# schematic.net
KiCad netlist of a schematic drawn in EAGLE
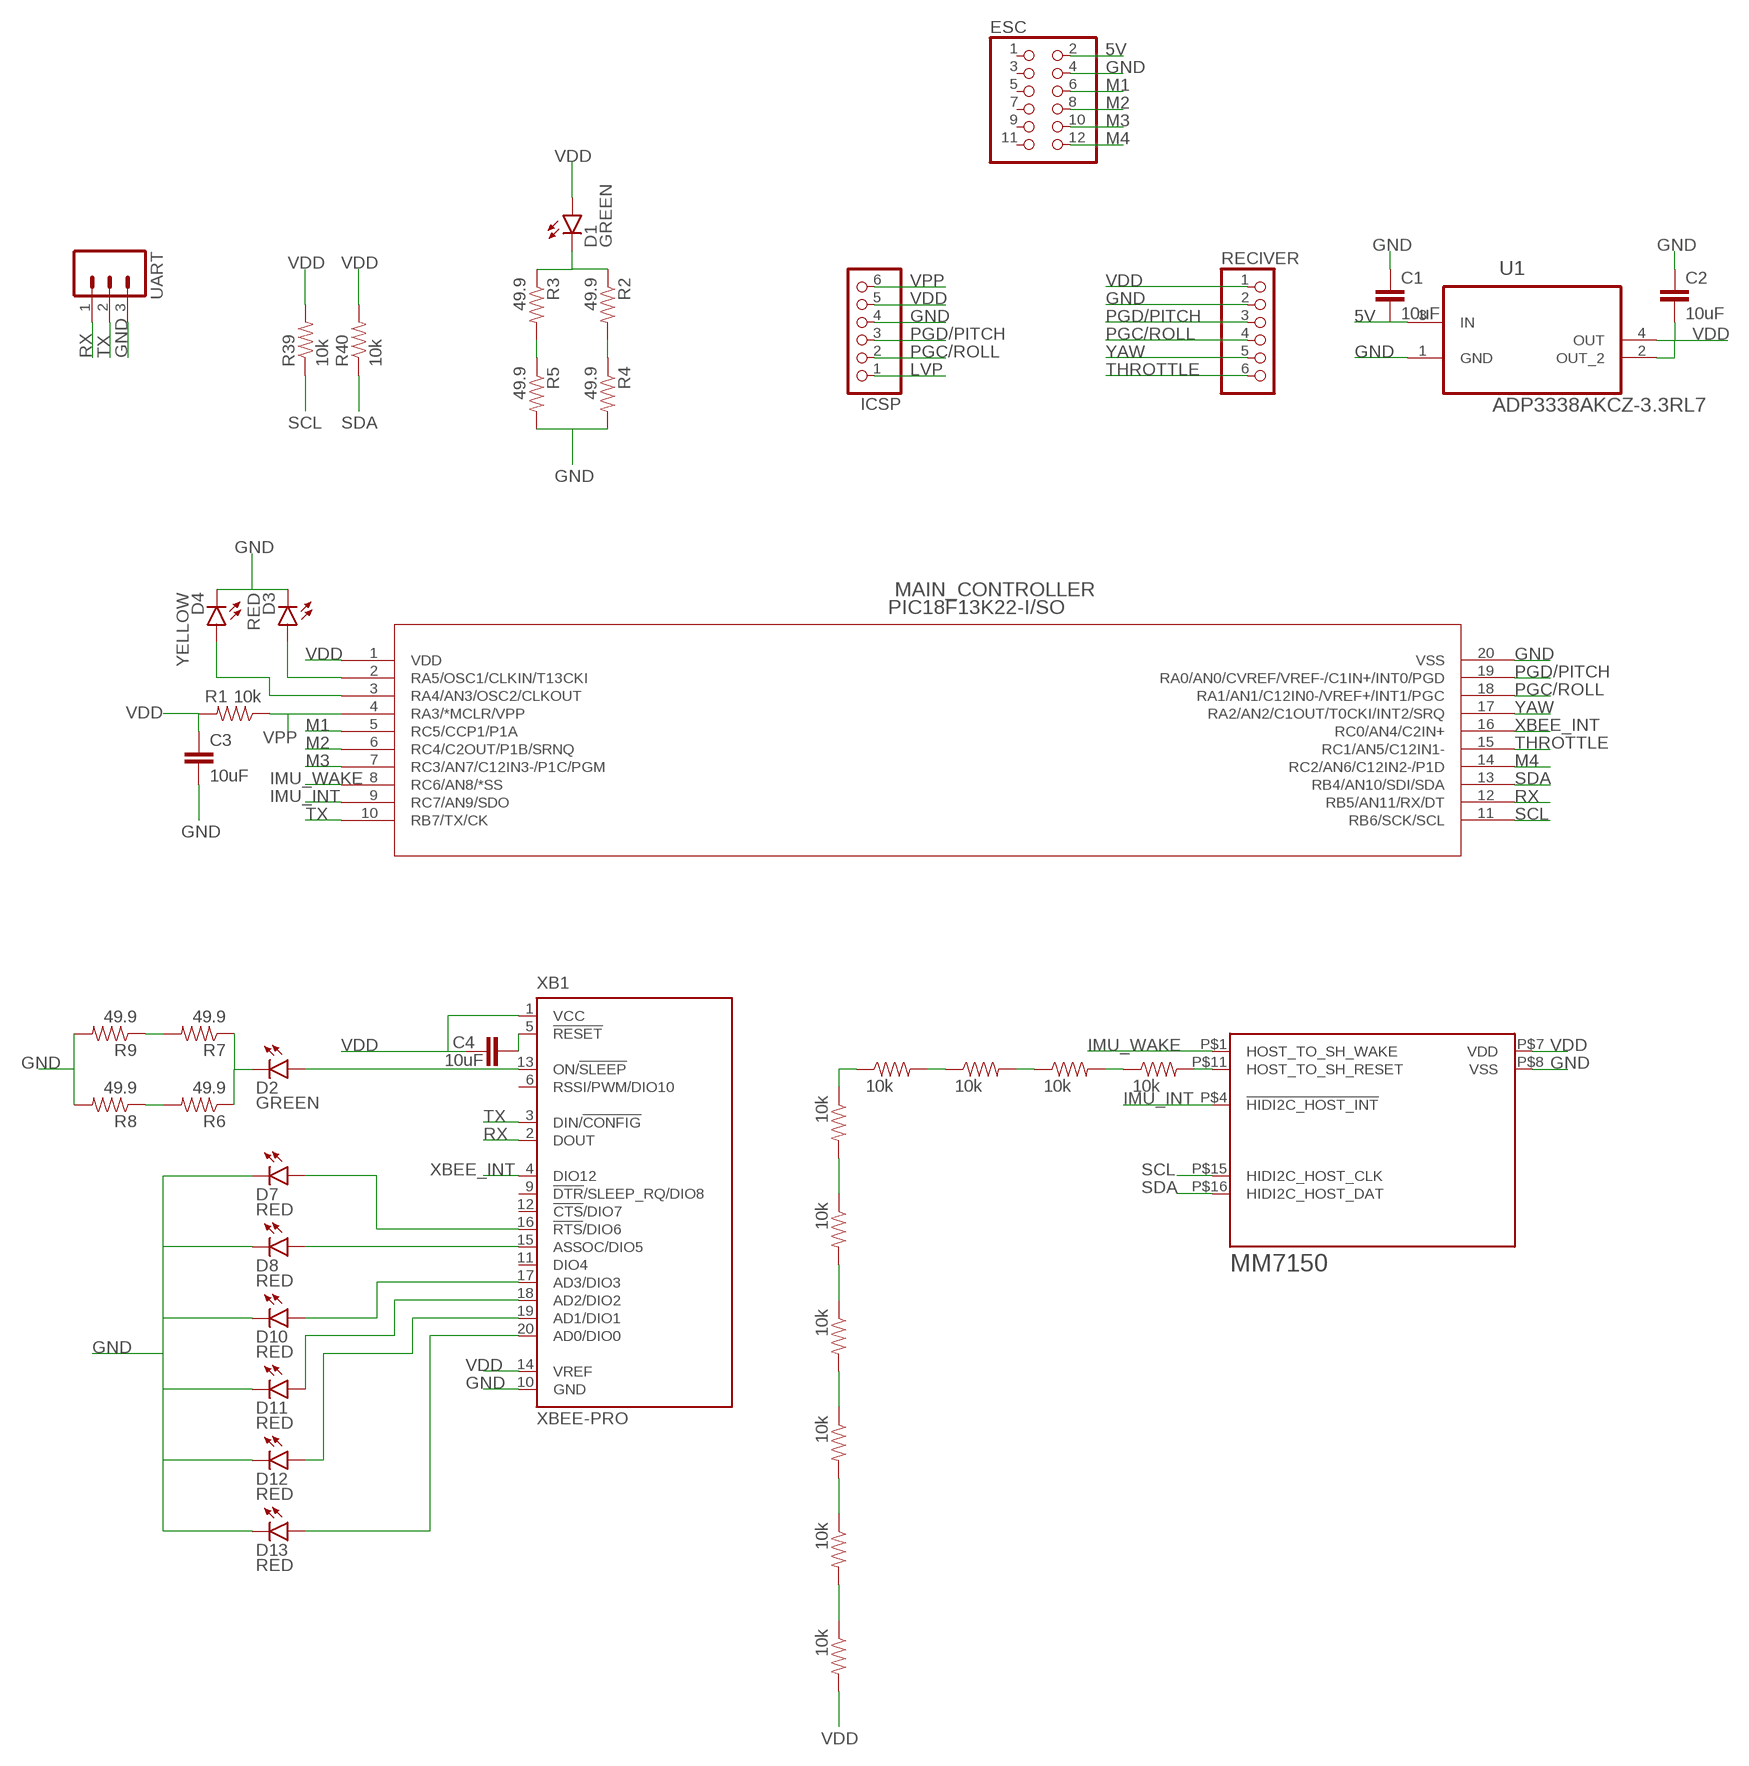
[diagram p0: schematic, sheet 1]

(export (version "E")
  (design (tool "Eeschema 10.0.6"))
  (components
    (comp (ref "C1")
      (value "10uF")
      (footprint "eagle-import:1210")
      (libsource (lib "eagle-import") (part "10UF50V20%(1210)"))
    )
    (comp (ref "C2")
      (value "10uF")
      (footprint "eagle-import:1210")
      (libsource (lib "eagle-import") (part "10UF50V20%(1210)"))
    )
    (comp (ref "C3")
      (value "10uF")
      (footprint "eagle-import:1210")
      (libsource (lib "eagle-import") (part "10UF50V20%(1210)"))
    )
    (comp (ref "C4")
      (value "10uF")
      (footprint "eagle-import:1210")
      (libsource (lib "eagle-import") (part "10UF50V20%(1210)"))
    )
    (comp (ref "D1")
      (value "GREEN")
      (footprint "eagle-import:LED-1206")
      (libsource (lib "eagle-import") (part "LED-GREEN1206"))
    )
    (comp (ref "D2")
      (value "GREEN")
      (footprint "eagle-import:LED-1206")
      (libsource (lib "eagle-import") (part "LED-GREEN1206"))
    )
    (comp (ref "D3")
      (value "RED")
      (footprint "eagle-import:LED-1206")
      (libsource (lib "eagle-import") (part "LED-RED1206"))
    )
    (comp (ref "D4")
      (value "YELLOW")
      (footprint "eagle-import:LED-1206")
      (libsource (lib "eagle-import") (part "LED-YELLOW1206"))
    )
    (comp (ref "D7")
      (value "RED")
      (footprint "eagle-import:LED-1206")
      (libsource (lib "eagle-import") (part "LED-RED1206"))
    )
    (comp (ref "D8")
      (value "RED")
      (footprint "eagle-import:LED-1206")
      (libsource (lib "eagle-import") (part "LED-RED1206"))
    )
    (comp (ref "D10")
      (value "RED")
      (footprint "eagle-import:LED-1206")
      (libsource (lib "eagle-import") (part "LED-RED1206"))
    )
    (comp (ref "D11")
      (value "RED")
      (footprint "eagle-import:LED-1206")
      (libsource (lib "eagle-import") (part "LED-RED1206"))
    )
    (comp (ref "D12")
      (value "RED")
      (footprint "eagle-import:LED-1206")
      (libsource (lib "eagle-import") (part "LED-RED1206"))
    )
    (comp (ref "D13")
      (value "RED")
      (footprint "eagle-import:LED-1206")
      (libsource (lib "eagle-import") (part "LED-RED1206"))
    )
    (comp (ref "ESC")
      (value "PINHD-2X6")
      (footprint "eagle-import:2X06")
      (libsource (lib "eagle-import") (part "PINHD-2X6"))
    )
    (comp (ref "ICSP")
      (value "PINHD-1X6/90")
      (footprint "eagle-import:1X06_90")
      (libsource (lib "eagle-import") (part "PINHD-1X6/90"))
    )
    (comp (ref "IMU")
      (value "MM7150")
      (footprint "eagle-import:LANDPATTERN")
      (libsource (lib "eagle-import") (part "MM7150"))
    )
    (comp (ref "MAIN_CONTROLLER")
      (value "PIC18F13K22-I/SO")
      (footprint "eagle-import:PIC18F13K22-X_SO")
      (libsource (lib "eagle-import") (part "PIC18F13K22-I/SO"))
    )
    (comp (ref "R1")
      (value "10k")
      (footprint "eagle-import:0402-RES")
      (libsource (lib "eagle-import") (part "RESISTOR0402-RES"))
    )
    (comp (ref "R2")
      (value "49.9")
      (footprint "eagle-import:0402-RES")
      (libsource (lib "eagle-import") (part "RESISTOR0402-RES"))
    )
    (comp (ref "R3")
      (value "49.9")
      (footprint "eagle-import:0402-RES")
      (libsource (lib "eagle-import") (part "RESISTOR0402-RES"))
    )
    (comp (ref "R4")
      (value "49.9")
      (footprint "eagle-import:0402-RES")
      (libsource (lib "eagle-import") (part "RESISTOR0402-RES"))
    )
    (comp (ref "R5")
      (value "49.9")
      (footprint "eagle-import:0402-RES")
      (libsource (lib "eagle-import") (part "RESISTOR0402-RES"))
    )
    (comp (ref "R6")
      (value "49.9")
      (footprint "eagle-import:0402-RES")
      (libsource (lib "eagle-import") (part "RESISTOR0402-RES"))
    )
    (comp (ref "R7")
      (value "49.9")
      (footprint "eagle-import:0402-RES")
      (libsource (lib "eagle-import") (part "RESISTOR0402-RES"))
    )
    (comp (ref "R8")
      (value "49.9")
      (footprint "eagle-import:0402-RES")
      (libsource (lib "eagle-import") (part "RESISTOR0402-RES"))
    )
    (comp (ref "R9")
      (value "49.9")
      (footprint "eagle-import:0402-RES")
      (libsource (lib "eagle-import") (part "RESISTOR0402-RES"))
    )
    (comp (ref "R10")
      (value "10k")
      (footprint "eagle-import:0402-RES")
      (libsource (lib "eagle-import") (part "RESISTOR0402-RES"))
    )
    (comp (ref "R11")
      (value "10k")
      (footprint "eagle-import:0402-RES")
      (libsource (lib "eagle-import") (part "RESISTOR0402-RES"))
    )
    (comp (ref "R12")
      (value "10k")
      (footprint "eagle-import:0402-RES")
      (libsource (lib "eagle-import") (part "RESISTOR0402-RES"))
    )
    (comp (ref "R13")
      (value "10k")
      (footprint "eagle-import:0402-RES")
      (libsource (lib "eagle-import") (part "RESISTOR0402-RES"))
    )
    (comp (ref "R14")
      (value "10k")
      (footprint "eagle-import:0402-RES")
      (libsource (lib "eagle-import") (part "RESISTOR0402-RES"))
    )
    (comp (ref "R15")
      (value "10k")
      (footprint "eagle-import:0402-RES")
      (libsource (lib "eagle-import") (part "RESISTOR0402-RES"))
    )
    (comp (ref "R16")
      (value "10k")
      (footprint "eagle-import:0402-RES")
      (libsource (lib "eagle-import") (part "RESISTOR0402-RES"))
    )
    (comp (ref "R17")
      (value "10k")
      (footprint "eagle-import:0402-RES")
      (libsource (lib "eagle-import") (part "RESISTOR0402-RES"))
    )
    (comp (ref "R18")
      (value "10k")
      (footprint "eagle-import:0402-RES")
      (libsource (lib "eagle-import") (part "RESISTOR0402-RES"))
    )
    (comp (ref "R19")
      (value "10k")
      (footprint "eagle-import:0402-RES")
      (libsource (lib "eagle-import") (part "RESISTOR0402-RES"))
    )
    (comp (ref "R39")
      (value "10k")
      (footprint "eagle-import:0402-RES")
      (libsource (lib "eagle-import") (part "RESISTOR0402-RES"))
    )
    (comp (ref "R40")
      (value "10k")
      (footprint "eagle-import:0402-RES")
      (libsource (lib "eagle-import") (part "RESISTOR0402-RES"))
    )
    (comp (ref "RECIVER")
      (value "PINHD-1X6")
      (footprint "eagle-import:1X06")
      (libsource (lib "eagle-import") (part "PINHD-1X6"))
    )
    (comp (ref "U1")
      (value "ADP3338AKCZ-3.3RL7")
      (footprint "eagle-import:SOT230P700X180-4N")
      (libsource (lib "eagle-import") (part "ADP3338AKCZ-3.3RL7"))
    )
    (comp (ref "UART")
      (value "M03LONGPADS")
      (footprint "eagle-import:1X03_LONGPADS")
      (libsource (lib "eagle-import") (part "M03LONGPADS"))
    )
    (comp (ref "XB1")
      (value "XBEE-PRO")
      (footprint "eagle-import:XBEE-PRO")
      (fields (field (name "MPN") "XBP24-AWI-001"))
      (libsource (lib "eagle-import") (part "XBEE-PRO"))
    )
  )
  (nets
    (net (code "1") (name "/5V") (class "Default")
      (node (ref "C1") (pin "2") (pinfunction "2_2") (pintype "passive"))
      (node (ref "ESC") (pin "2") (pinfunction "2_2") (pintype "passive"))
      (node (ref "U1") (pin "3") (pinfunction "IN_3") (pintype "input"))
    )
    (net (code "2") (name "/GND") (class "Default")
      (node (ref "C1") (pin "1") (pinfunction "1_1") (pintype "passive"))
      (node (ref "C2") (pin "1") (pinfunction "1_1") (pintype "passive"))
      (node (ref "C3") (pin "2") (pinfunction "2_2") (pintype "passive"))
      (node (ref "D10") (pin "C") (pinfunction "C_C") (pintype "passive"))
      (node (ref "D11") (pin "C") (pinfunction "C_C") (pintype "passive"))
      (node (ref "D12") (pin "C") (pinfunction "C_C") (pintype "passive"))
      (node (ref "D13") (pin "C") (pinfunction "C_C") (pintype "passive"))
      (node (ref "D3") (pin "C") (pinfunction "C_C") (pintype "passive"))
      (node (ref "D4") (pin "C") (pinfunction "C_C") (pintype "passive"))
      (node (ref "D7") (pin "C") (pinfunction "C_C") (pintype "passive"))
      (node (ref "D8") (pin "C") (pinfunction "C_C") (pintype "passive"))
      (node (ref "ESC") (pin "4") (pinfunction "4_4") (pintype "passive"))
      (node (ref "ICSP") (pin "4") (pinfunction "4_4") (pintype "passive"))
      (node (ref "IMU") (pin "P$8") (pinfunction "VSS_P$8") (pintype "power_in"))
      (node (ref "MAIN_CONTROLLER") (pin "20") (pinfunction "VSS_20") (pintype "power_in"))
      (node (ref "R4") (pin "2") (pinfunction "2_2") (pintype "passive"))
      (node (ref "R5") (pin "2") (pinfunction "2_2") (pintype "passive"))
      (node (ref "R8") (pin "2") (pinfunction "2_2") (pintype "passive"))
      (node (ref "R9") (pin "2") (pinfunction "2_2") (pintype "passive"))
      (node (ref "RECIVER") (pin "2") (pinfunction "2_2") (pintype "passive"))
      (node (ref "U1") (pin "1") (pinfunction "GND_1") (pintype "passive"))
      (node (ref "UART") (pin "3") (pinfunction "3_3") (pintype "passive"))
      (node (ref "XB1") (pin "10") (pinfunction "GND_10") (pintype "power_in"))
    )
    (net (code "3") (name "/IMU_INT") (class "Default")
      (node (ref "IMU") (pin "P$4") (pinfunction "~{HIDI2C_HOST_INT}_P$4") (pintype "output"))
      (node (ref "MAIN_CONTROLLER") (pin "9") (pinfunction "RC7/AN9/SDO_9") (pintype "bidirectional"))
    )
    (net (code "4") (name "/IMU_WAKE") (class "Default")
      (node (ref "IMU") (pin "P$1") (pinfunction "HOST_TO_SH_WAKE_P$1") (pintype "input"))
      (node (ref "MAIN_CONTROLLER") (pin "8") (pinfunction "RC6/AN8/*SS_8") (pintype "bidirectional"))
    )
    (net (code "5") (name "/LVP") (class "Default")
      (node (ref "ICSP") (pin "1") (pinfunction "1_1") (pintype "passive"))
    )
    (net (code "6") (name "/M1") (class "Default")
      (node (ref "ESC") (pin "6") (pinfunction "6_6") (pintype "passive"))
      (node (ref "MAIN_CONTROLLER") (pin "5") (pinfunction "RC5/CCP1/P1A_5") (pintype "bidirectional"))
    )
    (net (code "7") (name "/M2") (class "Default")
      (node (ref "ESC") (pin "8") (pinfunction "8_8") (pintype "passive"))
      (node (ref "MAIN_CONTROLLER") (pin "6") (pinfunction "RC4/C2OUT/P1B/SRNQ_6") (pintype "bidirectional"))
    )
    (net (code "8") (name "/M3") (class "Default")
      (node (ref "ESC") (pin "10") (pinfunction "10_10") (pintype "passive"))
      (node (ref "MAIN_CONTROLLER") (pin "7") (pinfunction "RC3/AN7/C12IN3-/P1C/PGM_7") (pintype "bidirectional"))
    )
    (net (code "9") (name "/M4") (class "Default")
      (node (ref "ESC") (pin "12") (pinfunction "12_12") (pintype "passive"))
      (node (ref "MAIN_CONTROLLER") (pin "14") (pinfunction "RC2/AN6/C12IN2-/P1D_14") (pintype "bidirectional"))
    )
    (net (code "10") (name "/PGC{slash}ROLL") (class "Default")
      (node (ref "ICSP") (pin "2") (pinfunction "2_2") (pintype "passive"))
      (node (ref "MAIN_CONTROLLER") (pin "18") (pinfunction "RA1/AN1/C12IN0-/VREF+/INT1/PGC_18") (pintype "bidirectional"))
      (node (ref "RECIVER") (pin "4") (pinfunction "4_4") (pintype "passive"))
    )
    (net (code "11") (name "/PGD{slash}PITCH") (class "Default")
      (node (ref "ICSP") (pin "3") (pinfunction "3_3") (pintype "passive"))
      (node (ref "MAIN_CONTROLLER") (pin "19") (pinfunction "RA0/AN0/CVREF/VREF-/C1IN+/INT0/PGD_19") (pintype "bidirectional"))
      (node (ref "RECIVER") (pin "3") (pinfunction "3_3") (pintype "passive"))
    )
    (net (code "12") (name "/RX") (class "Default")
      (node (ref "MAIN_CONTROLLER") (pin "12") (pinfunction "RB5/AN11/RX/DT_12") (pintype "bidirectional"))
      (node (ref "UART") (pin "1") (pinfunction "1_1") (pintype "passive"))
      (node (ref "XB1") (pin "2") (pinfunction "DOUT_2") (pintype "output"))
    )
    (net (code "13") (name "/SCL") (class "Default")
      (node (ref "IMU") (pin "P$15") (pinfunction "HIDI2C_HOST_CLK_P$15") (pintype "bidirectional"))
      (node (ref "MAIN_CONTROLLER") (pin "11") (pinfunction "RB6/SCK/SCL_11") (pintype "bidirectional"))
      (node (ref "R39") (pin "1") (pinfunction "1_1") (pintype "passive"))
    )
    (net (code "14") (name "/SDA") (class "Default")
      (node (ref "IMU") (pin "P$16") (pinfunction "HIDI2C_HOST_DAT_P$16") (pintype "bidirectional"))
      (node (ref "MAIN_CONTROLLER") (pin "13") (pinfunction "RB4/AN10/SDI/SDA_13") (pintype "bidirectional"))
      (node (ref "R40") (pin "1") (pinfunction "1_1") (pintype "passive"))
    )
    (net (code "15") (name "/THROTTLE") (class "Default")
      (node (ref "MAIN_CONTROLLER") (pin "15") (pinfunction "RC1/AN5/C12IN1-_15") (pintype "bidirectional"))
      (node (ref "RECIVER") (pin "6") (pinfunction "6_6") (pintype "passive"))
    )
    (net (code "16") (name "/TX") (class "Default")
      (node (ref "MAIN_CONTROLLER") (pin "10") (pinfunction "RB7/TX/CK_10") (pintype "bidirectional"))
      (node (ref "UART") (pin "2") (pinfunction "2_2") (pintype "passive"))
      (node (ref "XB1") (pin "3") (pinfunction "DIN/~{CONFIG}_3") (pintype "input"))
    )
    (net (code "17") (name "/VDD") (class "Default")
      (node (ref "C2") (pin "2") (pinfunction "2_2") (pintype "passive"))
      (node (ref "C3") (pin "1") (pinfunction "1_1") (pintype "passive"))
      (node (ref "C4") (pin "2") (pinfunction "2_2") (pintype "passive"))
      (node (ref "D1") (pin "A") (pinfunction "A_A") (pintype "passive"))
      (node (ref "ICSP") (pin "5") (pinfunction "5_5") (pintype "passive"))
      (node (ref "IMU") (pin "P$7") (pinfunction "VDD_P$7") (pintype "power_in"))
      (node (ref "MAIN_CONTROLLER") (pin "1") (pinfunction "VDD_1") (pintype "power_in"))
      (node (ref "R1") (pin "2") (pinfunction "2_2") (pintype "passive"))
      (node (ref "R19") (pin "2") (pinfunction "2_2") (pintype "passive"))
      (node (ref "R39") (pin "2") (pinfunction "2_2") (pintype "passive"))
      (node (ref "R40") (pin "2") (pinfunction "2_2") (pintype "passive"))
      (node (ref "RECIVER") (pin "1") (pinfunction "1_1") (pintype "passive"))
      (node (ref "U1") (pin "2") (pinfunction "OUT_2_2") (pintype "output"))
      (node (ref "U1") (pin "4") (pinfunction "OUT_4") (pintype "output"))
      (node (ref "XB1") (pin "1") (pinfunction "VCC_1") (pintype "power_in"))
      (node (ref "XB1") (pin "14") (pinfunction "VREF_14") (pintype "input"))
    )
    (net (code "18") (name "/VPP") (class "Default")
      (node (ref "ICSP") (pin "6") (pinfunction "6_6") (pintype "passive"))
      (node (ref "MAIN_CONTROLLER") (pin "4") (pinfunction "RA3/*MCLR/VPP_4") (pintype "bidirectional"))
      (node (ref "R1") (pin "1") (pinfunction "1_1") (pintype "passive"))
    )
    (net (code "19") (name "/XBEE_INT") (class "Default")
      (node (ref "MAIN_CONTROLLER") (pin "16") (pinfunction "RC0/AN4/C2IN+_16") (pintype "bidirectional"))
      (node (ref "XB1") (pin "4") (pinfunction "DIO12_4") (pintype "bidirectional"))
    )
    (net (code "20") (name "/YAW") (class "Default")
      (node (ref "MAIN_CONTROLLER") (pin "17") (pinfunction "RA2/AN2/C1OUT/T0CKI/INT2/SRQ_17") (pintype "bidirectional"))
      (node (ref "RECIVER") (pin "5") (pinfunction "5_5") (pintype "passive"))
    )
    (net (code "21") (name "Net-(D1-PadC)") (class "Default")
      (node (ref "D1") (pin "C") (pinfunction "C_C") (pintype "passive"))
      (node (ref "R2") (pin "1") (pinfunction "1_1") (pintype "passive"))
      (node (ref "R3") (pin "1") (pinfunction "1_1") (pintype "passive"))
    )
    (net (code "22") (name "Net-(D2-PadC)") (class "Default")
      (node (ref "D2") (pin "C") (pinfunction "C_C") (pintype "passive"))
      (node (ref "R6") (pin "1") (pinfunction "1_1") (pintype "passive"))
      (node (ref "R7") (pin "1") (pinfunction "1_1") (pintype "passive"))
    )
    (net (code "23") (name "Net-(IMU-HOST_TO_SH_RESET)") (class "Default")
      (node (ref "IMU") (pin "P$11") (pinfunction "HOST_TO_SH_RESET_P$11") (pintype "input"))
      (node (ref "R10") (pin "2") (pinfunction "2_2") (pintype "passive"))
    )
    (net (code "24") (name "Net-(MAIN_CONTROLLER-RA4{slash}AN3{slash}OSC2{slash}CLKOUT)") (class "Default")
      (node (ref "D4") (pin "A") (pinfunction "A_A") (pintype "passive"))
      (node (ref "MAIN_CONTROLLER") (pin "3") (pinfunction "RA4/AN3/OSC2/CLKOUT_3") (pintype "bidirectional"))
    )
    (net (code "25") (name "Net-(MAIN_CONTROLLER-RA5{slash}OSC1{slash}CLKIN{slash}T13CKI)") (class "Default")
      (node (ref "D3") (pin "A") (pinfunction "A_A") (pintype "passive"))
      (node (ref "MAIN_CONTROLLER") (pin "2") (pinfunction "RA5/OSC1/CLKIN/T13CKI_2") (pintype "bidirectional"))
    )
    (net (code "26") (name "Net-(R2-Pad2)") (class "Default")
      (node (ref "R2") (pin "2") (pinfunction "2_2") (pintype "passive"))
      (node (ref "R4") (pin "1") (pinfunction "1_1") (pintype "passive"))
    )
    (net (code "27") (name "Net-(R3-Pad2)") (class "Default")
      (node (ref "R3") (pin "2") (pinfunction "2_2") (pintype "passive"))
      (node (ref "R5") (pin "1") (pinfunction "1_1") (pintype "passive"))
    )
    (net (code "28") (name "Net-(R6-Pad2)") (class "Default")
      (node (ref "R6") (pin "2") (pinfunction "2_2") (pintype "passive"))
      (node (ref "R8") (pin "1") (pinfunction "1_1") (pintype "passive"))
    )
    (net (code "29") (name "Net-(R7-Pad2)") (class "Default")
      (node (ref "R7") (pin "2") (pinfunction "2_2") (pintype "passive"))
      (node (ref "R9") (pin "1") (pinfunction "1_1") (pintype "passive"))
    )
    (net (code "30") (name "Net-(R10-Pad1)") (class "Default")
      (node (ref "R10") (pin "1") (pinfunction "1_1") (pintype "passive"))
      (node (ref "R11") (pin "2") (pinfunction "2_2") (pintype "passive"))
    )
    (net (code "31") (name "Net-(R11-Pad1)") (class "Default")
      (node (ref "R11") (pin "1") (pinfunction "1_1") (pintype "passive"))
      (node (ref "R12") (pin "2") (pinfunction "2_2") (pintype "passive"))
    )
    (net (code "32") (name "Net-(R12-Pad1)") (class "Default")
      (node (ref "R12") (pin "1") (pinfunction "1_1") (pintype "passive"))
      (node (ref "R13") (pin "2") (pinfunction "2_2") (pintype "passive"))
    )
    (net (code "33") (name "Net-(R13-Pad1)") (class "Default")
      (node (ref "R13") (pin "1") (pinfunction "1_1") (pintype "passive"))
      (node (ref "R14") (pin "1") (pinfunction "1_1") (pintype "passive"))
    )
    (net (code "34") (name "Net-(R14-Pad2)") (class "Default")
      (node (ref "R14") (pin "2") (pinfunction "2_2") (pintype "passive"))
      (node (ref "R15") (pin "1") (pinfunction "1_1") (pintype "passive"))
    )
    (net (code "35") (name "Net-(R15-Pad2)") (class "Default")
      (node (ref "R15") (pin "2") (pinfunction "2_2") (pintype "passive"))
      (node (ref "R16") (pin "1") (pinfunction "1_1") (pintype "passive"))
    )
    (net (code "36") (name "Net-(R16-Pad2)") (class "Default")
      (node (ref "R16") (pin "2") (pinfunction "2_2") (pintype "passive"))
      (node (ref "R17") (pin "1") (pinfunction "1_1") (pintype "passive"))
    )
    (net (code "37") (name "Net-(R17-Pad2)") (class "Default")
      (node (ref "R17") (pin "2") (pinfunction "2_2") (pintype "passive"))
      (node (ref "R18") (pin "1") (pinfunction "1_1") (pintype "passive"))
    )
    (net (code "38") (name "Net-(R18-Pad2)") (class "Default")
      (node (ref "R18") (pin "2") (pinfunction "2_2") (pintype "passive"))
      (node (ref "R19") (pin "1") (pinfunction "1_1") (pintype "passive"))
    )
    (net (code "39") (name "Net-(XB1-AD0{slash}DIO0)") (class "Default")
      (node (ref "D13") (pin "A") (pinfunction "A_A") (pintype "passive"))
      (node (ref "XB1") (pin "20") (pinfunction "AD0/DIO0_20") (pintype "bidirectional"))
    )
    (net (code "40") (name "Net-(XB1-AD1{slash}DIO1)") (class "Default")
      (node (ref "D12") (pin "A") (pinfunction "A_A") (pintype "passive"))
      (node (ref "XB1") (pin "19") (pinfunction "AD1/DIO1_19") (pintype "bidirectional"))
    )
    (net (code "41") (name "Net-(XB1-AD2{slash}DIO2)") (class "Default")
      (node (ref "D11") (pin "A") (pinfunction "A_A") (pintype "passive"))
      (node (ref "XB1") (pin "18") (pinfunction "AD2/DIO2_18") (pintype "bidirectional"))
    )
    (net (code "42") (name "Net-(XB1-AD3{slash}DIO3)") (class "Default")
      (node (ref "D10") (pin "A") (pinfunction "A_A") (pintype "passive"))
      (node (ref "XB1") (pin "17") (pinfunction "AD3/DIO3_17") (pintype "bidirectional"))
    )
    (net (code "43") (name "Net-(XB1-ASSOC{slash}DIO5)") (class "Default")
      (node (ref "D8") (pin "A") (pinfunction "A_A") (pintype "passive"))
      (node (ref "XB1") (pin "15") (pinfunction "ASSOC/DIO5_15") (pintype "bidirectional"))
    )
    (net (code "44") (name "Net-(XB1-ON{slash}~{SLEEP})") (class "Default")
      (node (ref "D2") (pin "A") (pinfunction "A_A") (pintype "passive"))
      (node (ref "XB1") (pin "13") (pinfunction "ON/~{SLEEP}_13") (pintype "output"))
    )
    (net (code "45") (name "Net-(XB1-~{RESET})") (class "Default")
      (node (ref "C4") (pin "1") (pinfunction "1_1") (pintype "passive"))
      (node (ref "XB1") (pin "5") (pinfunction "~{RESET}_5") (pintype "input"))
    )
    (net (code "46") (name "Net-(XB1-~{RTS}{slash}DIO6)") (class "Default")
      (node (ref "D7") (pin "A") (pinfunction "A_A") (pintype "passive"))
      (node (ref "XB1") (pin "16") (pinfunction "~{RTS}/DIO6_16") (pintype "bidirectional"))
    )
    (net (code "47") (name "unconnected-(ESC-Pad1)") (class "Default")
      (node (ref "ESC") (pin "1") (pinfunction "1_1") (pintype "passive"))
    )
    (net (code "48") (name "unconnected-(ESC-Pad3)") (class "Default")
      (node (ref "ESC") (pin "3") (pinfunction "3_3") (pintype "passive"))
    )
    (net (code "49") (name "unconnected-(ESC-Pad5)") (class "Default")
      (node (ref "ESC") (pin "5") (pinfunction "5_5") (pintype "passive"))
    )
    (net (code "50") (name "unconnected-(ESC-Pad7)") (class "Default")
      (node (ref "ESC") (pin "7") (pinfunction "7_7") (pintype "passive"))
    )
    (net (code "51") (name "unconnected-(ESC-Pad9)") (class "Default")
      (node (ref "ESC") (pin "9") (pinfunction "9_9") (pintype "passive"))
    )
    (net (code "52") (name "unconnected-(ESC-Pad11)") (class "Default")
      (node (ref "ESC") (pin "11") (pinfunction "11_11") (pintype "passive"))
    )
    (net (code "53") (name "unconnected-(XB1-DIO4-Pad11)") (class "Default")
      (node (ref "XB1") (pin "11") (pinfunction "DIO4_11") (pintype "bidirectional"))
    )
    (net (code "54") (name "unconnected-(XB1-RSSI{slash}PWM{slash}DIO10-Pad6)") (class "Default")
      (node (ref "XB1") (pin "6") (pinfunction "RSSI/PWM/DIO10_6") (pintype "output"))
    )
    (net (code "55") (name "unconnected-(XB1-~{CTS}{slash}DIO7-Pad12)") (class "Default")
      (node (ref "XB1") (pin "12") (pinfunction "~{CTS}/DIO7_12") (pintype "bidirectional"))
    )
    (net (code "56") (name "unconnected-(XB1-~{DTR}{slash}SLEEP_RQ{slash}DIO8-Pad9)") (class "Default")
      (node (ref "XB1") (pin "9") (pinfunction "~{DTR}/SLEEP_RQ/DIO8_9") (pintype "bidirectional"))
    )
  )
)
